# Glasses-PSUBoard.net
KiCad netlist of a schematic drawn in Altium Designer
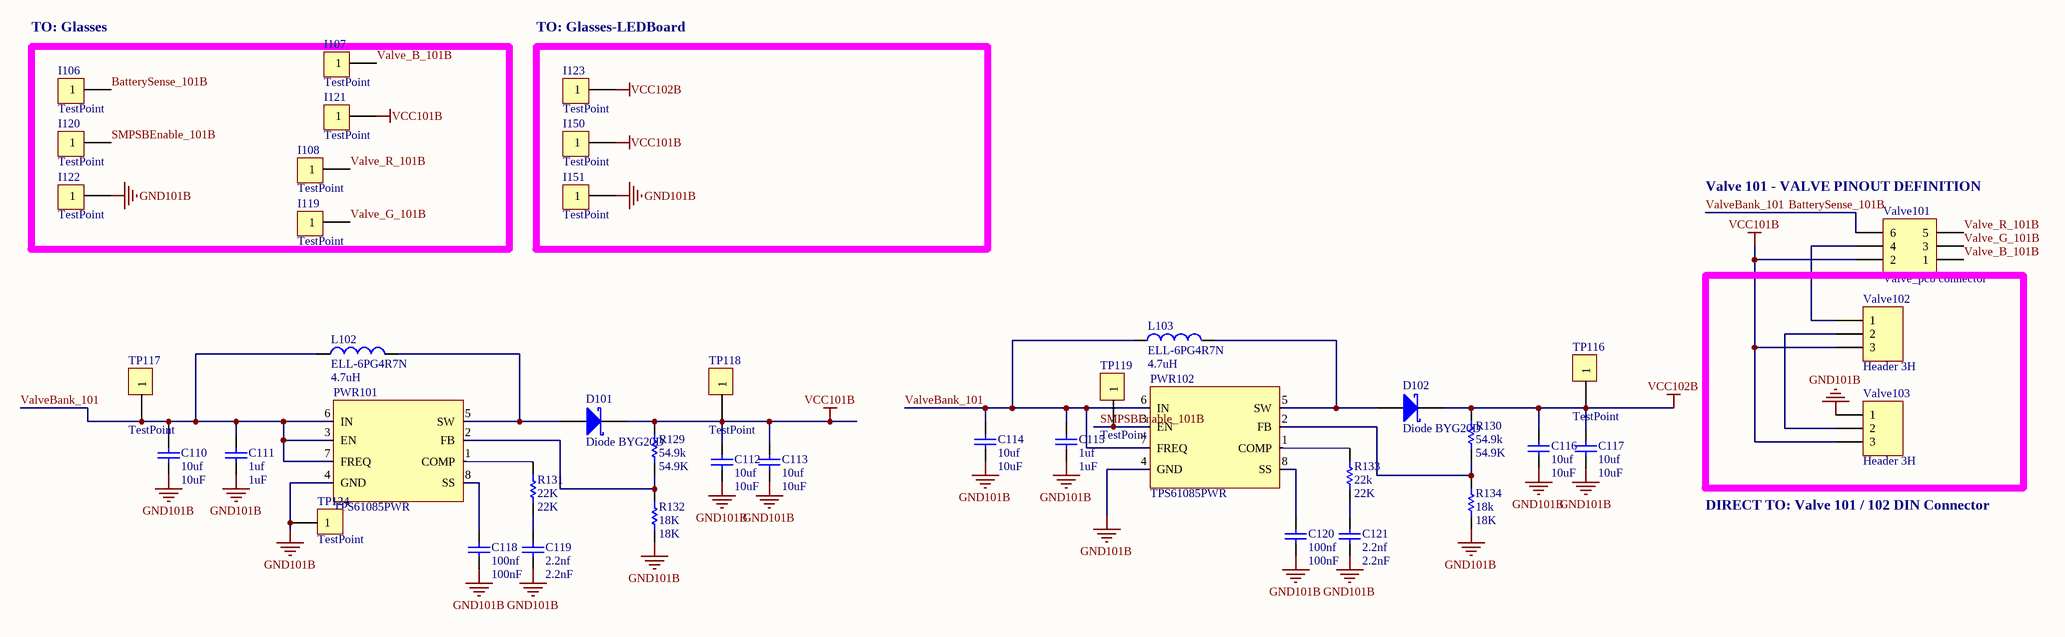
[diagram p0: Glasses-PSUBoard.SchDoc]

(export (version "E")
  (design (tool "Eeschema 10.0.6"))
  (components
    (comp (ref "C110")
      (value "10uf")
      (footprint "0805")
      (description "Capacitor (Semiconductor SIM Model)")
      (fields (field (name "ALTIUM_VALUE") "10uF") (field (name "PUBLISHER") "Altium Limited"))
      (libsource (lib "Miscellaneous Devices") (part "Cap Semi"))
    )
    (comp (ref "C111")
      (value "1uf")
      (footprint "0603")
      (description "Capacitor (Semiconductor SIM Model)")
      (fields (field (name "ALTIUM_VALUE") "1uF") (field (name "PUBLISHER") "Altium Limited"))
      (libsource (lib "Miscellaneous Devices") (part "Cap Semi"))
    )
    (comp (ref "C112")
      (value "10uf")
      (footprint "0805")
      (description "Capacitor (Semiconductor SIM Model)")
      (fields (field (name "ALTIUM_VALUE") "10uF") (field (name "PUBLISHER") "Altium Limited"))
      (libsource (lib "Miscellaneous Devices") (part "Cap Semi"))
    )
    (comp (ref "C113")
      (value "10uf")
      (footprint "0805")
      (description "Capacitor (Semiconductor SIM Model)")
      (fields (field (name "ALTIUM_VALUE") "10uF") (field (name "PUBLISHER") "Altium Limited"))
      (libsource (lib "Miscellaneous Devices") (part "Cap Semi"))
    )
    (comp (ref "C114")
      (value "10uf")
      (footprint "0805")
      (description "Capacitor (Semiconductor SIM Model)")
      (fields (field (name "ALTIUM_VALUE") "10uF") (field (name "PUBLISHER") "Altium Limited"))
      (libsource (lib "Miscellaneous Devices") (part "Cap Semi"))
    )
    (comp (ref "C115")
      (value "1uf")
      (footprint "0603")
      (description "Capacitor (Semiconductor SIM Model)")
      (fields (field (name "ALTIUM_VALUE") "1uF") (field (name "PUBLISHER") "Altium Limited"))
      (libsource (lib "Miscellaneous Devices") (part "Cap Semi"))
    )
    (comp (ref "C116")
      (value "10uf")
      (footprint "0805")
      (description "Capacitor (Semiconductor SIM Model)")
      (fields (field (name "ALTIUM_VALUE") "10uF") (field (name "PUBLISHER") "Altium Limited"))
      (libsource (lib "Miscellaneous Devices") (part "Cap Semi"))
    )
    (comp (ref "C117")
      (value "10uf")
      (footprint "0805")
      (description "Capacitor (Semiconductor SIM Model)")
      (fields (field (name "ALTIUM_VALUE") "10uF") (field (name "PUBLISHER") "Altium Limited"))
      (libsource (lib "Miscellaneous Devices") (part "Cap Semi"))
    )
    (comp (ref "C118")
      (value "100nf")
      (footprint "0603")
      (description "Capacitor (Semiconductor SIM Model)")
      (fields (field (name "ALTIUM_VALUE") "100nF") (field (name "PUBLISHER") "Altium Limited"))
      (libsource (lib "Miscellaneous Devices") (part "Cap Semi"))
    )
    (comp (ref "C119")
      (value "2.2nf")
      (footprint "0402")
      (description "Capacitor (Semiconductor SIM Model)")
      (fields (field (name "ALTIUM_VALUE") "2.2nF") (field (name "PUBLISHER") "Altium Limited"))
      (libsource (lib "Miscellaneous Devices") (part "Cap Semi"))
    )
    (comp (ref "C120")
      (value "100nf")
      (footprint "0603")
      (description "Capacitor (Semiconductor SIM Model)")
      (fields (field (name "ALTIUM_VALUE") "100nF") (field (name "PUBLISHER") "Altium Limited"))
      (libsource (lib "Miscellaneous Devices") (part "Cap Semi"))
    )
    (comp (ref "C121")
      (value "2.2nf")
      (footprint "0402")
      (description "Capacitor (Semiconductor SIM Model)")
      (fields (field (name "ALTIUM_VALUE") "2.2nF") (field (name "PUBLISHER") "Altium Limited"))
      (libsource (lib "Miscellaneous Devices") (part "Cap Semi"))
    )
    (comp (ref "D101")
      (value "Diode BYG20D")
      (footprint "BYG20J-E3")
      (description "Schottky Rectifier")
      (fields (field (name "PUBLISHER") "Altium Limited"))
      (libsource (lib "Miscellaneous Devices") (part "Diode 10TQ035"))
    )
    (comp (ref "D102")
      (value "Diode BYG20D")
      (footprint "BYG20J-E3")
      (description "Schottky Rectifier")
      (fields (field (name "PUBLISHER") "Altium Limited"))
      (libsource (lib "Miscellaneous Devices") (part "Diode 10TQ035"))
    )
    (comp (ref "I106") (value "TestPoint") (footprint "TestPoint") (libsource (lib "") (part "TestPoint_2")))
    (comp (ref "I107") (value "TestPoint") (footprint "TestPoint") (libsource (lib "") (part "TestPoint_2")))
    (comp (ref "I108") (value "TestPoint") (footprint "TestPoint") (libsource (lib "") (part "TestPoint_2")))
    (comp (ref "I119") (value "TestPoint") (footprint "TestPoint") (libsource (lib "") (part "TestPoint_2")))
    (comp (ref "I120") (value "TestPoint") (footprint "TestPoint") (libsource (lib "") (part "TestPoint_2")))
    (comp (ref "I121") (value "TestPoint") (footprint "TestPoint") (libsource (lib "") (part "TestPoint_2")))
    (comp (ref "I122") (value "TestPoint") (footprint "TestPoint") (libsource (lib "") (part "TestPoint_2")))
    (comp (ref "I123") (value "TestPoint") (footprint "TestPoint") (libsource (lib "") (part "TestPoint_2")))
    (comp (ref "I150") (value "TestPoint") (footprint "TestPoint") (libsource (lib "") (part "TestPoint_2")))
    (comp (ref "I151") (value "TestPoint") (footprint "TestPoint") (libsource (lib "") (part "TestPoint_2")))
    (comp (ref "L102")
      (value "ELL-6PG4R7N")
      (footprint "ELL6PG4R7N-2CHK")
      (description "Inductor")
      (fields (field (name "ALTIUM_VALUE") "4.7uH") (field (name "PUBLISHER") "Altium Limited"))
      (libsource (lib "Miscellaneous Devices") (part "Inductor"))
    )
    (comp (ref "L103")
      (value "ELL-6PG4R7N")
      (footprint "ELL6PG4R7N-2CHK")
      (description "Inductor")
      (fields (field (name "ALTIUM_VALUE") "4.7uH") (field (name "PUBLISHER") "Altium Limited"))
      (libsource (lib "Miscellaneous Devices") (part "Inductor"))
    )
    (comp (ref "PWR101")
      (value "TPS61085PWR")
      (footprint "TPS61085-MSOP8")
      (libsource (lib "Schlib1") (part "TPS61085PWR"))
    )
    (comp (ref "PWR102")
      (value "TPS61085PWR")
      (footprint "TPS61085-MSOP8")
      (libsource (lib "Schlib1") (part "TPS61085PWR"))
    )
    (comp (ref "R129")
      (value "54.9k")
      (footprint "0603")
      (description "Resistor")
      (fields (field (name "ALTIUM_VALUE") "54.9K") (field (name "PUBLISHER") "Altium Limited"))
      (libsource (lib "Miscellaneous Devices") (part "Res1"))
    )
    (comp (ref "R130")
      (value "54.9k")
      (footprint "0603")
      (description "Resistor")
      (fields (field (name "ALTIUM_VALUE") "54.9K") (field (name "PUBLISHER") "Altium Limited"))
      (libsource (lib "Miscellaneous Devices") (part "Res1"))
    )
    (comp (ref "R131")
      (value "22K")
      (footprint "0603")
      (description "Resistor")
      (fields (field (name "ALTIUM_VALUE") "22K") (field (name "PUBLISHER") "Altium Limited"))
      (libsource (lib "Miscellaneous Devices") (part "Res1"))
    )
    (comp (ref "R132")
      (value "18K")
      (footprint "0603")
      (description "Resistor")
      (fields (field (name "ALTIUM_VALUE") "18K") (field (name "PUBLISHER") "Altium Limited"))
      (libsource (lib "Miscellaneous Devices") (part "Res1"))
    )
    (comp (ref "R133")
      (value "22k")
      (footprint "0603")
      (description "Resistor")
      (fields (field (name "ALTIUM_VALUE") "22K") (field (name "PUBLISHER") "Altium Limited"))
      (libsource (lib "Miscellaneous Devices") (part "Res1"))
    )
    (comp (ref "R134")
      (value "18k")
      (footprint "0603")
      (description "Resistor")
      (fields (field (name "ALTIUM_VALUE") "18K") (field (name "PUBLISHER") "Altium Limited"))
      (libsource (lib "Miscellaneous Devices") (part "Res1"))
    )
    (comp (ref "TP116") (value "TestPoint") (footprint "TestPoint") (libsource (lib "") (part "TestPoint_1")))
    (comp (ref "TP117") (value "TestPoint") (footprint "TestPoint") (libsource (lib "") (part "TestPoint_1")))
    (comp (ref "TP118") (value "TestPoint") (footprint "TestPoint") (libsource (lib "") (part "TestPoint_1")))
    (comp (ref "TP119") (value "TestPoint") (footprint "TestPoint") (libsource (lib "") (part "TestPoint_1")))
    (comp (ref "TP124")
      (value "TestPoint")
      (footprint "TestPoint")
      (libsource (lib "Schlib1") (part "TestPoint"))
    )
    (comp (ref "Valve101")
      (value "Valve_pcb connector")
      (footprint "Valve_pcb mount")
      (description "Header, 3-Pin, Dual row, Right Angle")
      (fields (field (name "PUBLISHER") "Altium Limited"))
      (libsource (lib "Miscellaneous Connectors") (part "Header 3X2H"))
    )
    (comp (ref "Valve102")
      (value "Header 3H")
      (footprint "Valve_3 pin")
      (description "Header, 3-Pin, Right Angle")
      (fields (field (name "PUBLISHER") "Altium Limited"))
      (libsource (lib "Miscellaneous Connectors") (part "Header 3H"))
    )
    (comp (ref "Valve103")
      (value "Header 3H")
      (footprint "Valve_3 pin")
      (description "Header, 3-Pin, Right Angle")
      (fields (field (name "PUBLISHER") "Altium Limited"))
      (libsource (lib "Miscellaneous Connectors") (part "Header 3H"))
    )
  )
  (nets
    (net (code "1") (name "/BatterySense_101B") (class "Default")
      (node (ref "C110") (pin "2") (pinfunction "2_2") (pintype "passive"))
      (node (ref "C111") (pin "2") (pinfunction "2_2") (pintype "passive"))
      (node (ref "C114") (pin "2") (pinfunction "2_2") (pintype "passive"))
      (node (ref "C115") (pin "2") (pinfunction "2_2") (pintype "passive"))
      (node (ref "I106") (pin "1") (pinfunction "1_1") (pintype "passive"))
      (node (ref "L102") (pin "1") (pinfunction "1_1") (pintype "passive"))
      (node (ref "L103") (pin "1") (pinfunction "1_1") (pintype "passive"))
      (node (ref "PWR101") (pin "3") (pinfunction "EN_3") (pintype "passive"))
      (node (ref "PWR101") (pin "6") (pinfunction "IN_6") (pintype "passive"))
      (node (ref "PWR101") (pin "7") (pinfunction "FREQ_7") (pintype "passive"))
      (node (ref "PWR102") (pin "6") (pinfunction "IN_6") (pintype "passive"))
      (node (ref "PWR102") (pin "7") (pinfunction "FREQ_7") (pintype "passive"))
      (node (ref "TP117") (pin "1") (pinfunction "1_1") (pintype "passive"))
      (node (ref "Valve101") (pin "6") (pinfunction "6_6") (pintype "passive"))
    )
    (net (code "2") (name "/SMPSBEnable_101B") (class "Default")
      (node (ref "I120") (pin "1") (pinfunction "1_1") (pintype "passive"))
      (node (ref "PWR102") (pin "3") (pinfunction "EN_3") (pintype "passive"))
      (node (ref "TP119") (pin "1") (pinfunction "1_1") (pintype "passive"))
    )
    (net (code "3") (name "/Valve_B_101B") (class "Default")
      (node (ref "I107") (pin "1") (pinfunction "1_1") (pintype "passive"))
      (node (ref "Valve101") (pin "1") (pinfunction "1_1") (pintype "passive"))
    )
    (net (code "4") (name "/Valve_G_101B") (class "Default")
      (node (ref "I119") (pin "1") (pinfunction "1_1") (pintype "passive"))
      (node (ref "Valve101") (pin "3") (pinfunction "3_3") (pintype "passive"))
    )
    (net (code "5") (name "/Valve_R_101B") (class "Default")
      (node (ref "I108") (pin "1") (pinfunction "1_1") (pintype "passive"))
      (node (ref "Valve101") (pin "5") (pinfunction "5_5") (pintype "passive"))
    )
    (net (code "6") (name "GND101B") (class "Default")
      (node (ref "C110") (pin "1") (pinfunction "1_1") (pintype "passive"))
      (node (ref "C111") (pin "1") (pinfunction "1_1") (pintype "passive"))
      (node (ref "C112") (pin "1") (pinfunction "1_1") (pintype "passive"))
      (node (ref "C113") (pin "1") (pinfunction "1_1") (pintype "passive"))
      (node (ref "C114") (pin "1") (pinfunction "1_1") (pintype "passive"))
      (node (ref "C115") (pin "1") (pinfunction "1_1") (pintype "passive"))
      (node (ref "C116") (pin "1") (pinfunction "1_1") (pintype "passive"))
      (node (ref "C117") (pin "1") (pinfunction "1_1") (pintype "passive"))
      (node (ref "C118") (pin "1") (pinfunction "1_1") (pintype "passive"))
      (node (ref "C119") (pin "1") (pinfunction "1_1") (pintype "passive"))
      (node (ref "C120") (pin "1") (pinfunction "1_1") (pintype "passive"))
      (node (ref "C121") (pin "1") (pinfunction "1_1") (pintype "passive"))
      (node (ref "I122") (pin "1") (pinfunction "1_1") (pintype "passive"))
      (node (ref "I151") (pin "1") (pinfunction "1_1") (pintype "passive"))
      (node (ref "PWR101") (pin "4") (pinfunction "GND_4") (pintype "passive"))
      (node (ref "PWR102") (pin "4") (pinfunction "GND_4") (pintype "passive"))
      (node (ref "R132") (pin "1") (pinfunction "1_1") (pintype "passive"))
      (node (ref "R134") (pin "1") (pinfunction "1_1") (pintype "passive"))
      (node (ref "TP124") (pin "1") (pinfunction "1_1") (pintype "passive"))
      (node (ref "Valve103") (pin "1") (pinfunction "1_1") (pintype "passive"))
    )
    (net (code "7") (name "Net-(C119-Pad2)") (class "Default")
      (node (ref "C119") (pin "2") (pinfunction "2_2") (pintype "passive"))
      (node (ref "R131") (pin "1") (pinfunction "1_1") (pintype "passive"))
    )
    (net (code "8") (name "Net-(C121-Pad2)") (class "Default")
      (node (ref "C121") (pin "2") (pinfunction "2_2") (pintype "passive"))
      (node (ref "R133") (pin "1") (pinfunction "1_1") (pintype "passive"))
    )
    (net (code "9") (name "Net-(D101-A)") (class "Default")
      (node (ref "D101") (pin "3") (pinfunction "A_3") (pintype "passive"))
      (node (ref "L102") (pin "2") (pinfunction "2_2") (pintype "passive"))
      (node (ref "PWR101") (pin "5") (pinfunction "SW_5") (pintype "passive"))
    )
    (net (code "10") (name "Net-(D102-A)") (class "Default")
      (node (ref "D102") (pin "3") (pinfunction "A_3") (pintype "passive"))
      (node (ref "L103") (pin "2") (pinfunction "2_2") (pintype "passive"))
      (node (ref "PWR102") (pin "5") (pinfunction "SW_5") (pintype "passive"))
    )
    (net (code "11") (name "Net-(PWR101-COMP)") (class "Default")
      (node (ref "PWR101") (pin "1") (pinfunction "COMP_1") (pintype "passive"))
      (node (ref "R131") (pin "2") (pinfunction "2_2") (pintype "passive"))
    )
    (net (code "12") (name "Net-(PWR101-FB)") (class "Default")
      (node (ref "PWR101") (pin "2") (pinfunction "FB_2") (pintype "passive"))
      (node (ref "R129") (pin "1") (pinfunction "1_1") (pintype "passive"))
      (node (ref "R132") (pin "2") (pinfunction "2_2") (pintype "passive"))
    )
    (net (code "13") (name "Net-(PWR101-SS)") (class "Default")
      (node (ref "C118") (pin "2") (pinfunction "2_2") (pintype "passive"))
      (node (ref "PWR101") (pin "8") (pinfunction "SS_8") (pintype "passive"))
    )
    (net (code "14") (name "Net-(PWR102-COMP)") (class "Default")
      (node (ref "PWR102") (pin "1") (pinfunction "COMP_1") (pintype "passive"))
      (node (ref "R133") (pin "2") (pinfunction "2_2") (pintype "passive"))
    )
    (net (code "15") (name "Net-(PWR102-FB)") (class "Default")
      (node (ref "PWR102") (pin "2") (pinfunction "FB_2") (pintype "passive"))
      (node (ref "R130") (pin "1") (pinfunction "1_1") (pintype "passive"))
      (node (ref "R134") (pin "2") (pinfunction "2_2") (pintype "passive"))
    )
    (net (code "16") (name "Net-(PWR102-SS)") (class "Default")
      (node (ref "C120") (pin "2") (pinfunction "2_2") (pintype "passive"))
      (node (ref "PWR102") (pin "8") (pinfunction "SS_8") (pintype "passive"))
    )
    (net (code "17") (name "Net-(Valve101-Pad4)") (class "Default")
      (node (ref "Valve101") (pin "4") (pinfunction "4_4") (pintype "passive"))
      (node (ref "Valve102") (pin "1") (pinfunction "1_1") (pintype "passive"))
    )
    (net (code "18") (name "Net-(Valve102-Pad2)") (class "Default")
      (node (ref "Valve102") (pin "2") (pinfunction "2_2") (pintype "passive"))
      (node (ref "Valve103") (pin "2") (pinfunction "2_2") (pintype "passive"))
    )
    (net (code "19") (name "VCC101B") (class "Default")
      (node (ref "C112") (pin "2") (pinfunction "2_2") (pintype "passive"))
      (node (ref "C113") (pin "2") (pinfunction "2_2") (pintype "passive"))
      (node (ref "D101") (pin "1") (pinfunction "K_1") (pintype "passive"))
      (node (ref "I121") (pin "1") (pinfunction "1_1") (pintype "passive"))
      (node (ref "I150") (pin "1") (pinfunction "1_1") (pintype "passive"))
      (node (ref "R129") (pin "2") (pinfunction "2_2") (pintype "passive"))
      (node (ref "TP118") (pin "1") (pinfunction "1_1") (pintype "passive"))
      (node (ref "Valve101") (pin "2") (pinfunction "2_2") (pintype "passive"))
      (node (ref "Valve102") (pin "3") (pinfunction "3_3") (pintype "passive"))
      (node (ref "Valve103") (pin "3") (pinfunction "3_3") (pintype "passive"))
    )
    (net (code "20") (name "VCC102B") (class "Default")
      (node (ref "C116") (pin "2") (pinfunction "2_2") (pintype "passive"))
      (node (ref "C117") (pin "2") (pinfunction "2_2") (pintype "passive"))
      (node (ref "D102") (pin "1") (pinfunction "K_1") (pintype "passive"))
      (node (ref "I123") (pin "1") (pinfunction "1_1") (pintype "passive"))
      (node (ref "R130") (pin "2") (pinfunction "2_2") (pintype "passive"))
      (node (ref "TP116") (pin "1") (pinfunction "1_1") (pintype "passive"))
    )
  )
)
